# Low_Speed_Expansion.net
KiCad netlist of a schematic drawn in Altium Designer
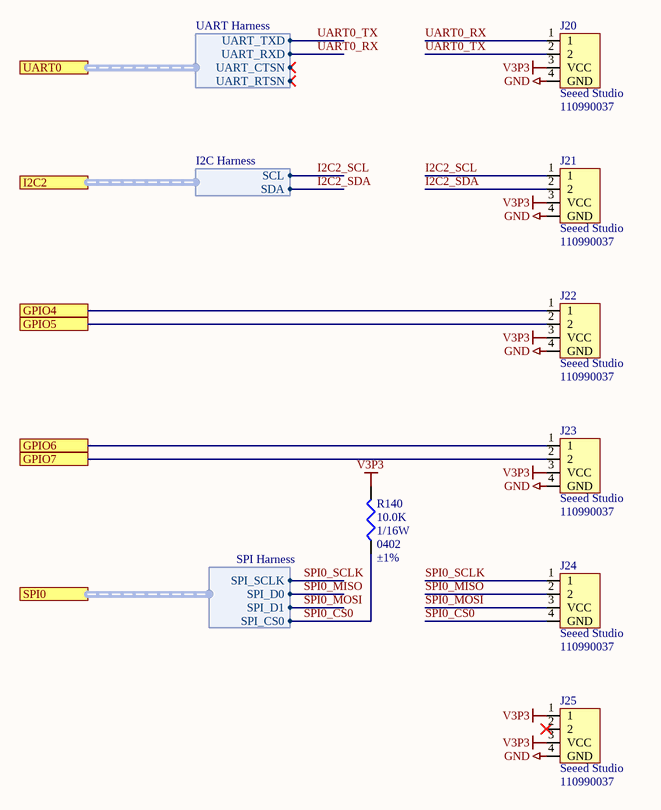
[diagram p0: Low Speed Expansion.SchDoc]

(export (version "E")
  (design (tool "Eeschema 10.0.6"))
  (components
    (comp (ref "J20")
      (value "320110034")
      (footprint "HW4-2.0-90D")
      (fields
        (field (name "MANUFACTURER 1") "Seeed Studio")
        (field (name "MANUFACTURER PART NUMBER 1") "110990037")
      )
      (libsource (lib "Cospan Design") (part "J_GROVE-CONNECTOR-DIP-90D(4P-2.0)"))
    )
    (comp (ref "J21")
      (value "320110034")
      (footprint "HW4-2.0-90D")
      (fields
        (field (name "MANUFACTURER 1") "Seeed Studio")
        (field (name "MANUFACTURER PART NUMBER 1") "110990037")
      )
      (libsource (lib "Cospan Design") (part "J_GROVE-CONNECTOR-DIP-90D(4P-2.0)"))
    )
    (comp (ref "J22")
      (value "320110034")
      (footprint "HW4-2.0-90D")
      (fields
        (field (name "MANUFACTURER 1") "Seeed Studio")
        (field (name "MANUFACTURER PART NUMBER 1") "110990037")
      )
      (libsource (lib "Cospan Design") (part "J_GROVE-CONNECTOR-DIP-90D(4P-2.0)"))
    )
    (comp (ref "J23")
      (value "320110034")
      (footprint "HW4-2.0-90D")
      (fields
        (field (name "MANUFACTURER 1") "Seeed Studio")
        (field (name "MANUFACTURER PART NUMBER 1") "110990037")
      )
      (libsource (lib "Cospan Design") (part "J_GROVE-CONNECTOR-DIP-90D(4P-2.0)"))
    )
    (comp (ref "J24")
      (value "320110034")
      (footprint "HW4-2.0-90D")
      (fields
        (field (name "MANUFACTURER 1") "Seeed Studio")
        (field (name "MANUFACTURER PART NUMBER 1") "110990037")
      )
      (libsource (lib "Cospan Design") (part "J_GROVE-CONNECTOR-DIP-90D(4P-2.0)"))
    )
    (comp (ref "J25")
      (value "320110034")
      (footprint "HW4-2.0-90D")
      (fields
        (field (name "MANUFACTURER 1") "Seeed Studio")
        (field (name "MANUFACTURER PART NUMBER 1") "110990037")
      )
      (libsource (lib "Cospan Design") (part "J_GROVE-CONNECTOR-DIP-90D(4P-2.0)"))
    )
    (comp (ref "R140")
      (value "R_0402_10.0K")
      (footprint "R_0402")
      (description "RES 10.0K OHM 1/16W 1% 0402 SMD")
      (fields
        (field (name "MANUFACTURER") "Stackpole Electronics Inc")
        (field (name "MANUFACTURER PART NUMBER") "RMCF0402FT10K0")
        (field (name "RESISTANCE IN OHMS") "10.0K")
        (field (name "POWER (WATTS)") "1/16W")
        (field (name "CASE") "0402")
        (field (name "TOLERANCE") "±1%")
      )
      (libsource (lib "Main Library") (part "R_0402_10.0K"))
    )
  )
  (nets
    (net (code "5") (name "/GPIO4") (class "Default")
      (node (ref "J22") (pin "1") (pinfunction "1_1") (pintype "passive"))
    )
    (net (code "6") (name "/GPIO5") (class "Default")
      (node (ref "J22") (pin "2") (pinfunction "2_2") (pintype "passive"))
    )
    (net (code "7") (name "/GPIO6") (class "Default")
      (node (ref "J23") (pin "1") (pinfunction "1_1") (pintype "passive"))
    )
    (net (code "8") (name "/GPIO7") (class "Default")
      (node (ref "J23") (pin "2") (pinfunction "2_2") (pintype "passive"))
    )
    (net (code "9") (name "/I2C2_SCL") (class "Default")
      (node (ref "J21") (pin "1") (pinfunction "1_1") (pintype "passive"))
    )
    (net (code "10") (name "/I2C2_SDA") (class "Default")
      (node (ref "J21") (pin "2") (pinfunction "2_2") (pintype "passive"))
    )
    (net (code "11") (name "/SPI0_CS0") (class "Default")
      (node (ref "J24") (pin "4") (pinfunction "GND_4") (pintype "passive"))
      (node (ref "R140") (pin "2") (pinfunction "2_2") (pintype "passive"))
    )
    (net (code "12") (name "/SPI0_MISO") (class "Default")
      (node (ref "J24") (pin "2") (pinfunction "2_2") (pintype "passive"))
    )
    (net (code "13") (name "/SPI0_MOSI") (class "Default")
      (node (ref "J24") (pin "3") (pinfunction "VCC_3") (pintype "passive"))
    )
    (net (code "14") (name "/SPI0_SCLK") (class "Default")
      (node (ref "J24") (pin "1") (pinfunction "1_1") (pintype "passive"))
    )
    (net (code "15") (name "/UART0_RX") (class "Default")
      (node (ref "J20") (pin "1") (pinfunction "1_1") (pintype "passive"))
    )
    (net (code "16") (name "/UART0_TX") (class "Default")
      (node (ref "J20") (pin "2") (pinfunction "2_2") (pintype "passive"))
    )
    (net (code "20") (name "GND") (class "Default")
      (node (ref "J20") (pin "4") (pinfunction "GND_4") (pintype "passive"))
      (node (ref "J21") (pin "4") (pinfunction "GND_4") (pintype "passive"))
      (node (ref "J22") (pin "4") (pinfunction "GND_4") (pintype "passive"))
      (node (ref "J23") (pin "4") (pinfunction "GND_4") (pintype "passive"))
      (node (ref "J25") (pin "4") (pinfunction "GND_4") (pintype "passive"))
    )
    (net (code "21") (name "V3P3") (class "Default")
      (node (ref "J20") (pin "3") (pinfunction "VCC_3") (pintype "passive"))
      (node (ref "J21") (pin "3") (pinfunction "VCC_3") (pintype "passive"))
      (node (ref "J22") (pin "3") (pinfunction "VCC_3") (pintype "passive"))
      (node (ref "J23") (pin "3") (pinfunction "VCC_3") (pintype "passive"))
      (node (ref "J25") (pin "1") (pinfunction "1_1") (pintype "passive"))
      (node (ref "J25") (pin "3") (pinfunction "VCC_3") (pintype "passive"))
      (node (ref "R140") (pin "1") (pinfunction "1_1") (pintype "passive"))
    )
    (net (code "22") (name "unconnected-(J25-Pad2)") (class "Default")
      (node (ref "J25") (pin "2") (pinfunction "2_2") (pintype "passive+no_connect"))
    )
  )
)
